# EstlcamShield.net
KiCad netlist of a schematic drawn in EAGLE
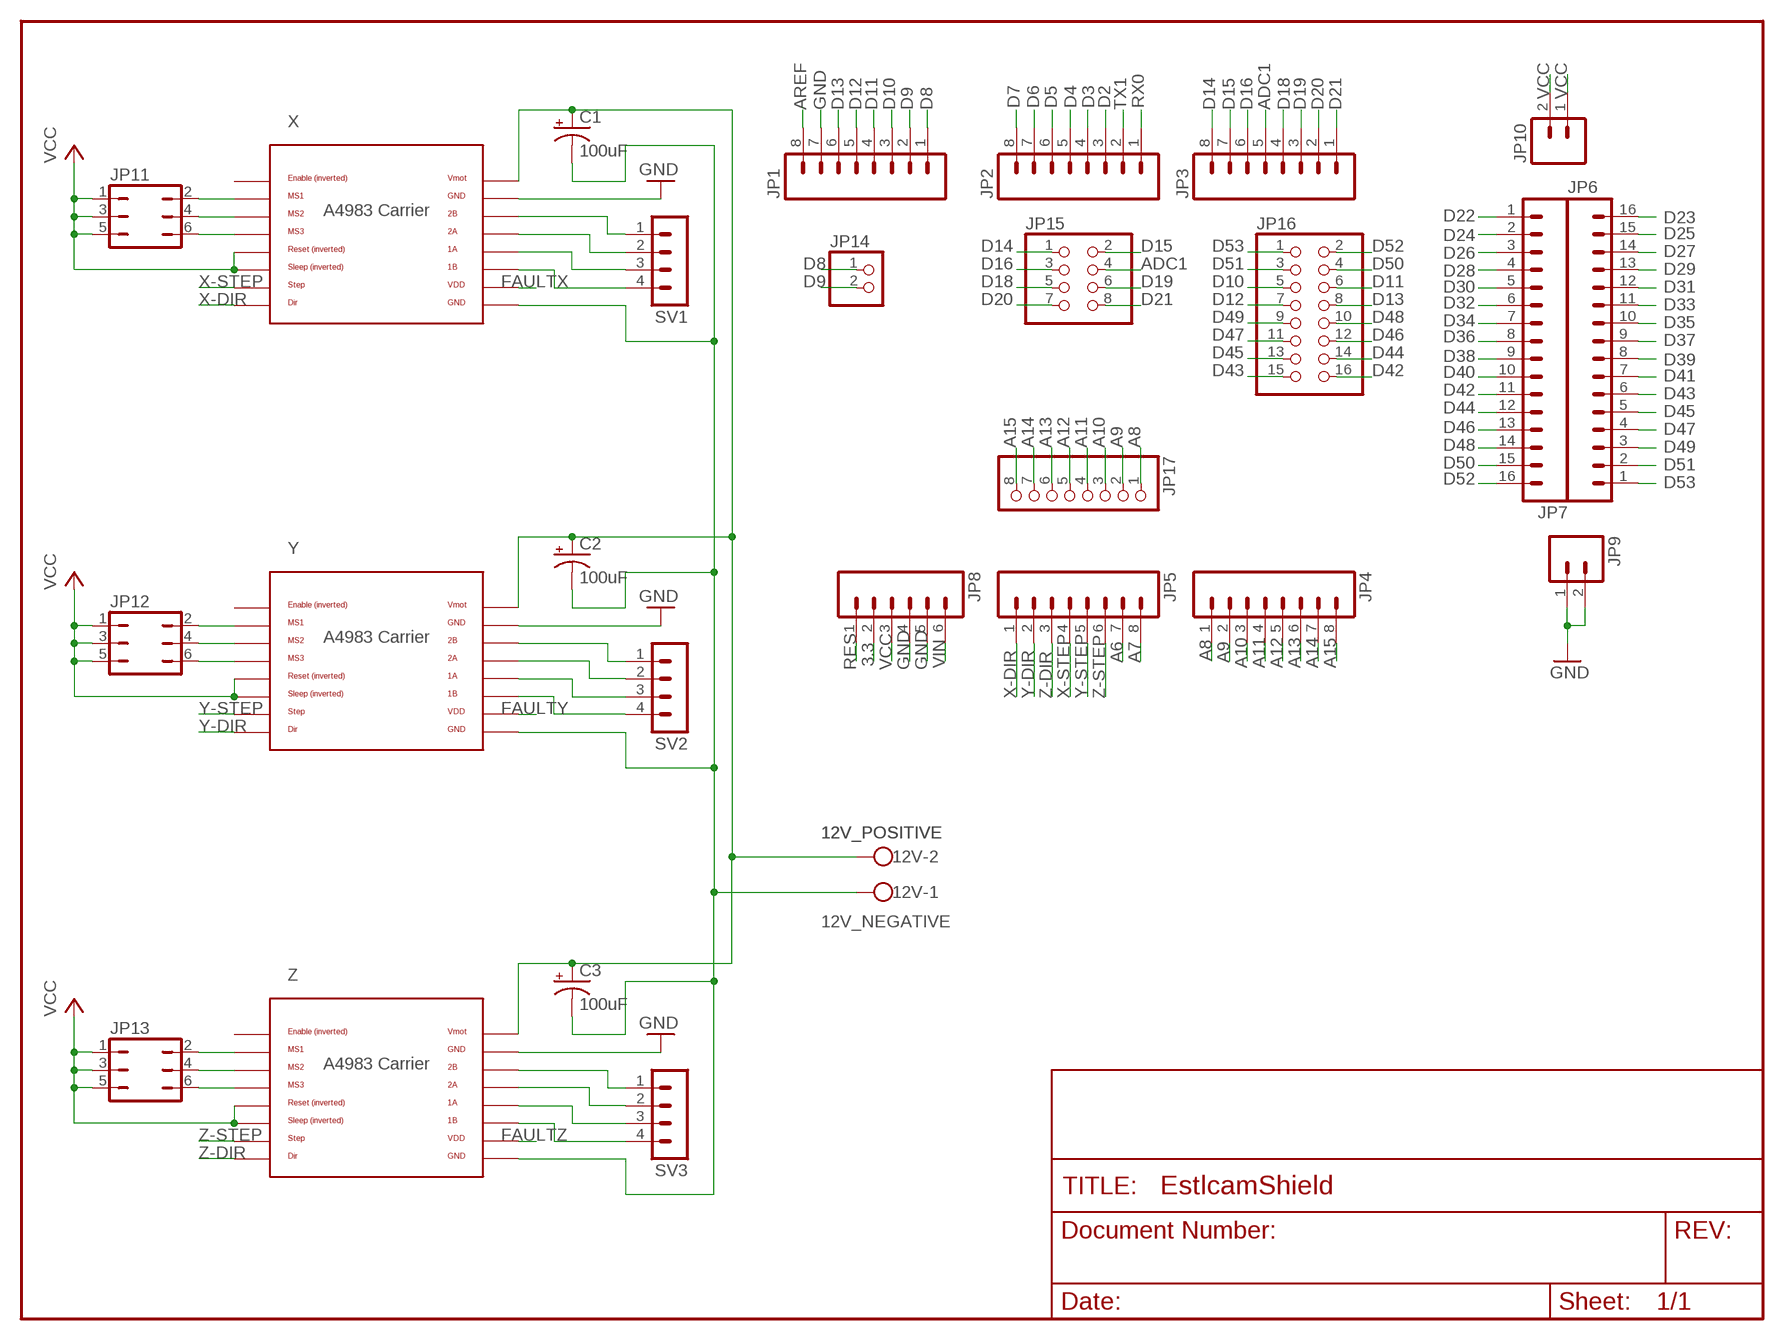
[diagram p0: schematic, sheet 1]

(export (version "E")
  (design (tool "Eeschema 10.0.6"))
  (components
    (comp (ref "12V")
      (value "POSITIVE")
      (footprint "eagle-import:W237-102")
      (fields (field (name "MPN") "237-102"))
      (libsource (lib "eagle-import") (part "W237-102"))
    )
    (comp (ref "C1")
      (value "100uF")
      (footprint "eagle-import:E2,5-5")
      (libsource (lib "eagle-import") (part "CPOL-USE2.5-5"))
    )
    (comp (ref "C2")
      (value "100uF")
      (footprint "eagle-import:E2,5-5")
      (libsource (lib "eagle-import") (part "CPOL-USE2.5-5"))
    )
    (comp (ref "C3")
      (value "100uF")
      (footprint "eagle-import:E2,5-5")
      (libsource (lib "eagle-import") (part "CPOL-USE2.5-5"))
    )
    (comp (ref "JP1")
      (value "M08LOCK")
      (footprint "eagle-import:1X08_LOCK")
      (libsource (lib "eagle-import") (part "M08LOCK"))
    )
    (comp (ref "JP2")
      (value "M08LOCK")
      (footprint "eagle-import:1X08_LOCK")
      (libsource (lib "eagle-import") (part "M08LOCK"))
    )
    (comp (ref "JP3")
      (value "M08LOCK")
      (footprint "eagle-import:1X08_LOCK")
      (libsource (lib "eagle-import") (part "M08LOCK"))
    )
    (comp (ref "JP4")
      (value "M08LOCK")
      (footprint "eagle-import:1X08_LOCK")
      (libsource (lib "eagle-import") (part "M08LOCK"))
    )
    (comp (ref "JP5")
      (value "M08LOCK")
      (footprint "eagle-import:1X08_LOCK")
      (libsource (lib "eagle-import") (part "M08LOCK"))
    )
    (comp (ref "JP6")
      (value "M16LOCK")
      (footprint "eagle-import:1X16_LOCK")
      (libsource (lib "eagle-import") (part "M16LOCK"))
    )
    (comp (ref "JP7")
      (value "M16LOCK")
      (footprint "eagle-import:1X16_LOCK")
      (libsource (lib "eagle-import") (part "M16LOCK"))
    )
    (comp (ref "JP8")
      (value "M06LOCK")
      (footprint "eagle-import:1X06_LOCK")
      (libsource (lib "eagle-import") (part "M06LOCK"))
    )
    (comp (ref "JP9")
      (value "M02LOCK")
      (footprint "eagle-import:1X02_LOCK")
      (libsource (lib "eagle-import") (part "M02LOCK"))
    )
    (comp (ref "JP10")
      (value "M02LOCK")
      (footprint "eagle-import:1X02_LOCK")
      (libsource (lib "eagle-import") (part "M02LOCK"))
    )
    (comp (ref "JP11")
      (value "JP3Q")
      (footprint "eagle-import:JP3Q")
      (libsource (lib "eagle-import") (part "JP3Q"))
    )
    (comp (ref "JP12")
      (value "JP3Q")
      (footprint "eagle-import:JP3Q")
      (libsource (lib "eagle-import") (part "JP3Q"))
    )
    (comp (ref "JP13")
      (value "JP3Q")
      (footprint "eagle-import:JP3Q")
      (libsource (lib "eagle-import") (part "JP3Q"))
    )
    (comp (ref "JP14")
      (value "PINHD-1X2")
      (footprint "eagle-import:1X02")
      (libsource (lib "eagle-import") (part "PINHD-1X2"))
    )
    (comp (ref "JP15")
      (value "PINHD-2X4")
      (footprint "eagle-import:2X04")
      (libsource (lib "eagle-import") (part "PINHD-2X4"))
    )
    (comp (ref "JP16")
      (value "PINHD-2X8")
      (footprint "eagle-import:2X08")
      (libsource (lib "eagle-import") (part "PINHD-2X8"))
    )
    (comp (ref "JP17")
      (value "PINHD-1X8")
      (footprint "eagle-import:1X08")
      (libsource (lib "eagle-import") (part "PINHD-1X8"))
    )
    (comp (ref "SV1")
      (value "MA04-1")
      (footprint "eagle-import:MA04-1")
      (libsource (lib "eagle-import") (part "MA04-1"))
    )
    (comp (ref "SV2")
      (value "MA04-1")
      (footprint "eagle-import:MA04-1")
      (libsource (lib "eagle-import") (part "MA04-1"))
    )
    (comp (ref "SV3")
      (value "MA04-1")
      (footprint "eagle-import:MA04-1")
      (libsource (lib "eagle-import") (part "MA04-1"))
    )
    (comp (ref "U2")
      (value "POLOLU_A4983CARRIER")
      (footprint "eagle-import:A4983CARRIER")
      (libsource (lib "eagle-import") (part "POLOLU_A4983CARRIER"))
    )
    (comp (ref "U3")
      (value "POLOLU_A4983CARRIER")
      (footprint "eagle-import:A4983CARRIER")
      (libsource (lib "eagle-import") (part "POLOLU_A4983CARRIER"))
    )
    (comp (ref "U4")
      (value "POLOLU_A4983CARRIER")
      (footprint "eagle-import:A4983CARRIER")
      (libsource (lib "eagle-import") (part "POLOLU_A4983CARRIER"))
    )
  )
  (nets
    (net (code "1") (name "/3.3") (class "Default")
      (node (ref "JP8") (pin "2") (pinfunction "2_2") (pintype "passive"))
    )
    (net (code "2") (name "/12V_NEGATIVE") (class "Default")
      (node (ref "12V") (pin "1") (pinfunction "KL_1") (pintype "passive"))
      (node (ref "C1") (pin "-") (pinfunction "-_-") (pintype "passive"))
      (node (ref "C2") (pin "-") (pinfunction "-_-") (pintype "passive"))
      (node (ref "C3") (pin "-") (pinfunction "-_-") (pintype "passive"))
      (node (ref "U2") (pin "GND@0") (pinfunction "GND_GND@0") (pintype "power_in"))
      (node (ref "U3") (pin "GND@0") (pinfunction "GND_GND@0") (pintype "power_in"))
      (node (ref "U4") (pin "GND@0") (pinfunction "GND_GND@0") (pintype "power_in"))
    )
    (net (code "3") (name "/12V_POSITIVE") (class "Default")
      (node (ref "12V") (pin "2") (pinfunction "KL_2") (pintype "passive"))
      (node (ref "C1") (pin "+") (pinfunction "+_+") (pintype "passive"))
      (node (ref "C2") (pin "+") (pinfunction "+_+") (pintype "passive"))
      (node (ref "C3") (pin "+") (pinfunction "+_+") (pintype "passive"))
      (node (ref "U2") (pin "VMOT") (pinfunction "VMOT_VMOT") (pintype "power_in"))
      (node (ref "U3") (pin "VMOT") (pinfunction "VMOT_VMOT") (pintype "power_in"))
      (node (ref "U4") (pin "VMOT") (pinfunction "VMOT_VMOT") (pintype "power_in"))
    )
    (net (code "4") (name "/A6") (class "Default")
      (node (ref "JP5") (pin "7") (pinfunction "7_7") (pintype "passive"))
    )
    (net (code "5") (name "/A7") (class "Default")
      (node (ref "JP5") (pin "8") (pinfunction "8_8") (pintype "passive"))
    )
    (net (code "6") (name "/A8") (class "Default")
      (node (ref "JP17") (pin "1") (pinfunction "1_1") (pintype "passive"))
      (node (ref "JP4") (pin "1") (pinfunction "1_1") (pintype "passive"))
    )
    (net (code "7") (name "/A9") (class "Default")
      (node (ref "JP17") (pin "2") (pinfunction "2_2") (pintype "passive"))
      (node (ref "JP4") (pin "2") (pinfunction "2_2") (pintype "passive"))
    )
    (net (code "8") (name "/A10") (class "Default")
      (node (ref "JP17") (pin "3") (pinfunction "3_3") (pintype "passive"))
      (node (ref "JP4") (pin "3") (pinfunction "3_3") (pintype "passive"))
    )
    (net (code "9") (name "/A11") (class "Default")
      (node (ref "JP17") (pin "4") (pinfunction "4_4") (pintype "passive"))
      (node (ref "JP4") (pin "4") (pinfunction "4_4") (pintype "passive"))
    )
    (net (code "10") (name "/A12") (class "Default")
      (node (ref "JP17") (pin "5") (pinfunction "5_5") (pintype "passive"))
      (node (ref "JP4") (pin "5") (pinfunction "5_5") (pintype "passive"))
    )
    (net (code "11") (name "/A13") (class "Default")
      (node (ref "JP17") (pin "6") (pinfunction "6_6") (pintype "passive"))
      (node (ref "JP4") (pin "6") (pinfunction "6_6") (pintype "passive"))
    )
    (net (code "12") (name "/A14") (class "Default")
      (node (ref "JP17") (pin "7") (pinfunction "7_7") (pintype "passive"))
      (node (ref "JP4") (pin "7") (pinfunction "7_7") (pintype "passive"))
    )
    (net (code "13") (name "/A15") (class "Default")
      (node (ref "JP17") (pin "8") (pinfunction "8_8") (pintype "passive"))
      (node (ref "JP4") (pin "8") (pinfunction "8_8") (pintype "passive"))
    )
    (net (code "14") (name "/ADC1") (class "Default")
      (node (ref "JP15") (pin "4") (pinfunction "4_4") (pintype "passive"))
      (node (ref "JP3") (pin "5") (pinfunction "5_5") (pintype "passive"))
    )
    (net (code "15") (name "/AREF") (class "Default")
      (node (ref "JP1") (pin "8") (pinfunction "8_8") (pintype "passive"))
    )
    (net (code "16") (name "/D2") (class "Default")
      (node (ref "JP2") (pin "3") (pinfunction "3_3") (pintype "passive"))
    )
    (net (code "17") (name "/D3") (class "Default")
      (node (ref "JP2") (pin "4") (pinfunction "4_4") (pintype "passive"))
    )
    (net (code "18") (name "/D4") (class "Default")
      (node (ref "JP2") (pin "5") (pinfunction "5_5") (pintype "passive"))
    )
    (net (code "19") (name "/D5") (class "Default")
      (node (ref "JP2") (pin "6") (pinfunction "6_6") (pintype "passive"))
    )
    (net (code "20") (name "/D6") (class "Default")
      (node (ref "JP2") (pin "7") (pinfunction "7_7") (pintype "passive"))
    )
    (net (code "21") (name "/D7") (class "Default")
      (node (ref "JP2") (pin "8") (pinfunction "8_8") (pintype "passive"))
    )
    (net (code "22") (name "/D8") (class "Default")
      (node (ref "JP1") (pin "1") (pinfunction "1_1") (pintype "passive"))
      (node (ref "JP14") (pin "1") (pinfunction "1_1") (pintype "passive"))
    )
    (net (code "23") (name "/D9") (class "Default")
      (node (ref "JP1") (pin "2") (pinfunction "2_2") (pintype "passive"))
      (node (ref "JP14") (pin "2") (pinfunction "2_2") (pintype "passive"))
    )
    (net (code "24") (name "/D10") (class "Default")
      (node (ref "JP1") (pin "3") (pinfunction "3_3") (pintype "passive"))
      (node (ref "JP16") (pin "5") (pinfunction "5_5") (pintype "passive"))
    )
    (net (code "25") (name "/D11") (class "Default")
      (node (ref "JP1") (pin "4") (pinfunction "4_4") (pintype "passive"))
      (node (ref "JP16") (pin "6") (pinfunction "6_6") (pintype "passive"))
    )
    (net (code "26") (name "/D12") (class "Default")
      (node (ref "JP1") (pin "5") (pinfunction "5_5") (pintype "passive"))
      (node (ref "JP16") (pin "7") (pinfunction "7_7") (pintype "passive"))
    )
    (net (code "27") (name "/D13") (class "Default")
      (node (ref "JP1") (pin "6") (pinfunction "6_6") (pintype "passive"))
      (node (ref "JP16") (pin "8") (pinfunction "8_8") (pintype "passive"))
    )
    (net (code "28") (name "/D14") (class "Default")
      (node (ref "JP15") (pin "1") (pinfunction "1_1") (pintype "passive"))
      (node (ref "JP3") (pin "8") (pinfunction "8_8") (pintype "passive"))
    )
    (net (code "29") (name "/D15") (class "Default")
      (node (ref "JP15") (pin "2") (pinfunction "2_2") (pintype "passive"))
      (node (ref "JP3") (pin "7") (pinfunction "7_7") (pintype "passive"))
    )
    (net (code "30") (name "/D16") (class "Default")
      (node (ref "JP15") (pin "3") (pinfunction "3_3") (pintype "passive"))
      (node (ref "JP3") (pin "6") (pinfunction "6_6") (pintype "passive"))
    )
    (net (code "31") (name "/D18") (class "Default")
      (node (ref "JP15") (pin "5") (pinfunction "5_5") (pintype "passive"))
      (node (ref "JP3") (pin "4") (pinfunction "4_4") (pintype "passive"))
    )
    (net (code "32") (name "/D19") (class "Default")
      (node (ref "JP15") (pin "6") (pinfunction "6_6") (pintype "passive"))
      (node (ref "JP3") (pin "3") (pinfunction "3_3") (pintype "passive"))
    )
    (net (code "33") (name "/D20") (class "Default")
      (node (ref "JP15") (pin "7") (pinfunction "7_7") (pintype "passive"))
      (node (ref "JP3") (pin "2") (pinfunction "2_2") (pintype "passive"))
    )
    (net (code "34") (name "/D21") (class "Default")
      (node (ref "JP15") (pin "8") (pinfunction "8_8") (pintype "passive"))
      (node (ref "JP3") (pin "1") (pinfunction "1_1") (pintype "passive"))
    )
    (net (code "35") (name "/D22") (class "Default")
      (node (ref "JP7") (pin "1") (pinfunction "1_1") (pintype "passive"))
    )
    (net (code "36") (name "/D23") (class "Default")
      (node (ref "JP6") (pin "16") (pinfunction "16_16") (pintype "passive"))
    )
    (net (code "37") (name "/D24") (class "Default")
      (node (ref "JP7") (pin "2") (pinfunction "2_2") (pintype "passive"))
    )
    (net (code "38") (name "/D25") (class "Default")
      (node (ref "JP6") (pin "15") (pinfunction "15_15") (pintype "passive"))
    )
    (net (code "39") (name "/D26") (class "Default")
      (node (ref "JP7") (pin "3") (pinfunction "3_3") (pintype "passive"))
    )
    (net (code "40") (name "/D27") (class "Default")
      (node (ref "JP6") (pin "14") (pinfunction "14_14") (pintype "passive"))
    )
    (net (code "41") (name "/D28") (class "Default")
      (node (ref "JP7") (pin "4") (pinfunction "4_4") (pintype "passive"))
    )
    (net (code "42") (name "/D29") (class "Default")
      (node (ref "JP6") (pin "13") (pinfunction "13_13") (pintype "passive"))
    )
    (net (code "43") (name "/D30") (class "Default")
      (node (ref "JP7") (pin "5") (pinfunction "5_5") (pintype "passive"))
    )
    (net (code "44") (name "/D31") (class "Default")
      (node (ref "JP6") (pin "12") (pinfunction "12_12") (pintype "passive"))
    )
    (net (code "45") (name "/D32") (class "Default")
      (node (ref "JP7") (pin "6") (pinfunction "6_6") (pintype "passive"))
    )
    (net (code "46") (name "/D33") (class "Default")
      (node (ref "JP6") (pin "11") (pinfunction "11_11") (pintype "passive"))
    )
    (net (code "47") (name "/D34") (class "Default")
      (node (ref "JP7") (pin "7") (pinfunction "7_7") (pintype "passive"))
    )
    (net (code "48") (name "/D35") (class "Default")
      (node (ref "JP6") (pin "10") (pinfunction "10_10") (pintype "passive"))
    )
    (net (code "49") (name "/D36") (class "Default")
      (node (ref "JP7") (pin "8") (pinfunction "8_8") (pintype "passive"))
    )
    (net (code "50") (name "/D37") (class "Default")
      (node (ref "JP6") (pin "9") (pinfunction "9_9") (pintype "passive"))
    )
    (net (code "51") (name "/D38") (class "Default")
      (node (ref "JP7") (pin "9") (pinfunction "9_9") (pintype "passive"))
    )
    (net (code "52") (name "/D39") (class "Default")
      (node (ref "JP6") (pin "8") (pinfunction "8_8") (pintype "passive"))
    )
    (net (code "53") (name "/D40") (class "Default")
      (node (ref "JP7") (pin "10") (pinfunction "10_10") (pintype "passive"))
    )
    (net (code "54") (name "/D41") (class "Default")
      (node (ref "JP6") (pin "7") (pinfunction "7_7") (pintype "passive"))
    )
    (net (code "55") (name "/D42") (class "Default")
      (node (ref "JP16") (pin "16") (pinfunction "16_16") (pintype "passive"))
      (node (ref "JP7") (pin "11") (pinfunction "11_11") (pintype "passive"))
    )
    (net (code "56") (name "/D43") (class "Default")
      (node (ref "JP16") (pin "15") (pinfunction "15_15") (pintype "passive"))
      (node (ref "JP6") (pin "6") (pinfunction "6_6") (pintype "passive"))
    )
    (net (code "57") (name "/D44") (class "Default")
      (node (ref "JP16") (pin "14") (pinfunction "14_14") (pintype "passive"))
      (node (ref "JP7") (pin "12") (pinfunction "12_12") (pintype "passive"))
    )
    (net (code "58") (name "/D45") (class "Default")
      (node (ref "JP16") (pin "13") (pinfunction "13_13") (pintype "passive"))
      (node (ref "JP6") (pin "5") (pinfunction "5_5") (pintype "passive"))
    )
    (net (code "59") (name "/D46") (class "Default")
      (node (ref "JP16") (pin "12") (pinfunction "12_12") (pintype "passive"))
      (node (ref "JP7") (pin "13") (pinfunction "13_13") (pintype "passive"))
    )
    (net (code "60") (name "/D47") (class "Default")
      (node (ref "JP16") (pin "11") (pinfunction "11_11") (pintype "passive"))
      (node (ref "JP6") (pin "4") (pinfunction "4_4") (pintype "passive"))
    )
    (net (code "61") (name "/D48") (class "Default")
      (node (ref "JP16") (pin "10") (pinfunction "10_10") (pintype "passive"))
      (node (ref "JP7") (pin "14") (pinfunction "14_14") (pintype "passive"))
    )
    (net (code "62") (name "/D49") (class "Default")
      (node (ref "JP16") (pin "9") (pinfunction "9_9") (pintype "passive"))
      (node (ref "JP6") (pin "3") (pinfunction "3_3") (pintype "passive"))
    )
    (net (code "63") (name "/D50") (class "Default")
      (node (ref "JP16") (pin "4") (pinfunction "4_4") (pintype "passive"))
      (node (ref "JP7") (pin "15") (pinfunction "15_15") (pintype "passive"))
    )
    (net (code "64") (name "/D51") (class "Default")
      (node (ref "JP16") (pin "3") (pinfunction "3_3") (pintype "passive"))
      (node (ref "JP6") (pin "2") (pinfunction "2_2") (pintype "passive"))
    )
    (net (code "65") (name "/D52") (class "Default")
      (node (ref "JP16") (pin "2") (pinfunction "2_2") (pintype "passive"))
      (node (ref "JP7") (pin "16") (pinfunction "16_16") (pintype "passive"))
    )
    (net (code "66") (name "/D53") (class "Default")
      (node (ref "JP16") (pin "1") (pinfunction "1_1") (pintype "passive"))
      (node (ref "JP6") (pin "1") (pinfunction "1_1") (pintype "passive"))
    )
    (net (code "67") (name "/FAULTX") (class "Default")
      (node (ref "U2") (pin "VDD") (pinfunction "VDD_VDD") (pintype "power_in"))
    )
    (net (code "68") (name "/FAULTY") (class "Default")
      (node (ref "U3") (pin "VDD") (pinfunction "VDD_VDD") (pintype "power_in"))
    )
    (net (code "69") (name "/FAULTZ") (class "Default")
      (node (ref "U4") (pin "VDD") (pinfunction "VDD_VDD") (pintype "power_in"))
    )
    (net (code "70") (name "/RES") (class "Default")
      (node (ref "JP8") (pin "1") (pinfunction "1_1") (pintype "passive"))
    )
    (net (code "71") (name "/RX0") (class "Default")
      (node (ref "JP2") (pin "1") (pinfunction "1_1") (pintype "passive"))
    )
    (net (code "72") (name "/TX1") (class "Default")
      (node (ref "JP2") (pin "2") (pinfunction "2_2") (pintype "passive"))
    )
    (net (code "73") (name "/VIN") (class "Default")
      (node (ref "JP8") (pin "6") (pinfunction "6_6") (pintype "passive"))
    )
    (net (code "74") (name "/X-DIR") (class "Default")
      (node (ref "JP5") (pin "1") (pinfunction "1_1") (pintype "passive"))
      (node (ref "U2") (pin "DIR") (pinfunction "DIR_DIR") (pintype "input"))
    )
    (net (code "75") (name "/X-STEP") (class "Default")
      (node (ref "JP5") (pin "4") (pinfunction "4_4") (pintype "passive"))
      (node (ref "U2") (pin "STEP") (pinfunction "STEP_STEP") (pintype "input"))
    )
    (net (code "76") (name "/Y-DIR") (class "Default")
      (node (ref "JP5") (pin "2") (pinfunction "2_2") (pintype "passive"))
      (node (ref "U3") (pin "DIR") (pinfunction "DIR_DIR") (pintype "input"))
    )
    (net (code "77") (name "/Y-STEP") (class "Default")
      (node (ref "JP5") (pin "5") (pinfunction "5_5") (pintype "passive"))
      (node (ref "U3") (pin "STEP") (pinfunction "STEP_STEP") (pintype "input"))
    )
    (net (code "78") (name "/Z-DIR") (class "Default")
      (node (ref "JP5") (pin "3") (pinfunction "3_3") (pintype "passive"))
      (node (ref "U4") (pin "DIR") (pinfunction "DIR_DIR") (pintype "input"))
    )
    (net (code "79") (name "/Z-STEP") (class "Default")
      (node (ref "JP5") (pin "6") (pinfunction "6_6") (pintype "passive"))
      (node (ref "U4") (pin "STEP") (pinfunction "STEP_STEP") (pintype "input"))
    )
    (net (code "80") (name "GND") (class "Default")
      (node (ref "JP1") (pin "7") (pinfunction "7_7") (pintype "passive"))
      (node (ref "JP8") (pin "4") (pinfunction "4_4") (pintype "passive"))
      (node (ref "JP8") (pin "5") (pinfunction "5_5") (pintype "passive"))
      (node (ref "JP9") (pin "1") (pinfunction "1_1") (pintype "passive"))
      (node (ref "JP9") (pin "2") (pinfunction "2_2") (pintype "passive"))
      (node (ref "U2") (pin "GND") (pinfunction "GND_GND") (pintype "power_in"))
      (node (ref "U3") (pin "GND") (pinfunction "GND_GND") (pintype "power_in"))
      (node (ref "U4") (pin "GND") (pinfunction "GND_GND") (pintype "power_in"))
    )
    (net (code "81") (name "Net-(JP11-Pad2)") (class "Default")
      (node (ref "JP11") (pin "2") (pinfunction "2_2") (pintype "passive"))
      (node (ref "U2") (pin "MS1") (pinfunction "MS1_MS1") (pintype "input"))
    )
    (net (code "82") (name "Net-(JP11-Pad4)") (class "Default")
      (node (ref "JP11") (pin "4") (pinfunction "4_4") (pintype "passive"))
      (node (ref "U2") (pin "MS2") (pinfunction "MS2_MS2") (pintype "input"))
    )
    (net (code "83") (name "Net-(JP11-Pad6)") (class "Default")
      (node (ref "JP11") (pin "6") (pinfunction "6_6") (pintype "passive"))
      (node (ref "U2") (pin "MS3") (pinfunction "MS3_MS3") (pintype "input"))
    )
    (net (code "84") (name "Net-(JP12-Pad2)") (class "Default")
      (node (ref "JP12") (pin "2") (pinfunction "2_2") (pintype "passive"))
      (node (ref "U3") (pin "MS1") (pinfunction "MS1_MS1") (pintype "input"))
    )
    (net (code "85") (name "Net-(JP12-Pad4)") (class "Default")
      (node (ref "JP12") (pin "4") (pinfunction "4_4") (pintype "passive"))
      (node (ref "U3") (pin "MS2") (pinfunction "MS2_MS2") (pintype "input"))
    )
    (net (code "86") (name "Net-(JP12-Pad6)") (class "Default")
      (node (ref "JP12") (pin "6") (pinfunction "6_6") (pintype "passive"))
      (node (ref "U3") (pin "MS3") (pinfunction "MS3_MS3") (pintype "input"))
    )
    (net (code "87") (name "Net-(JP13-Pad2)") (class "Default")
      (node (ref "JP13") (pin "2") (pinfunction "2_2") (pintype "passive"))
      (node (ref "U4") (pin "MS1") (pinfunction "MS1_MS1") (pintype "input"))
    )
    (net (code "88") (name "Net-(JP13-Pad4)") (class "Default")
      (node (ref "JP13") (pin "4") (pinfunction "4_4") (pintype "passive"))
      (node (ref "U4") (pin "MS2") (pinfunction "MS2_MS2") (pintype "input"))
    )
    (net (code "89") (name "Net-(JP13-Pad6)") (class "Default")
      (node (ref "JP13") (pin "6") (pinfunction "6_6") (pintype "passive"))
      (node (ref "U4") (pin "MS3") (pinfunction "MS3_MS3") (pintype "input"))
    )
    (net (code "90") (name "Net-(SV1-Pad1)") (class "Default")
      (node (ref "SV1") (pin "1") (pinfunction "1_1") (pintype "passive"))
      (node (ref "U2") (pin "2B") (pinfunction "2B_2B") (pintype "output"))
    )
    (net (code "91") (name "Net-(SV1-Pad2)") (class "Default")
      (node (ref "SV1") (pin "2") (pinfunction "2_2") (pintype "passive"))
      (node (ref "U2") (pin "2A") (pinfunction "2A_2A") (pintype "output"))
    )
    (net (code "92") (name "Net-(SV1-Pad3)") (class "Default")
      (node (ref "SV1") (pin "3") (pinfunction "3_3") (pintype "passive"))
      (node (ref "U2") (pin "1A") (pinfunction "1A_1A") (pintype "output"))
    )
    (net (code "93") (name "Net-(SV1-Pad4)") (class "Default")
      (node (ref "SV1") (pin "4") (pinfunction "4_4") (pintype "passive"))
      (node (ref "U2") (pin "1B") (pinfunction "1B_1B") (pintype "output"))
    )
    (net (code "94") (name "Net-(SV2-Pad1)") (class "Default")
      (node (ref "SV2") (pin "1") (pinfunction "1_1") (pintype "passive"))
      (node (ref "U3") (pin "2B") (pinfunction "2B_2B") (pintype "output"))
    )
    (net (code "95") (name "Net-(SV2-Pad2)") (class "Default")
      (node (ref "SV2") (pin "2") (pinfunction "2_2") (pintype "passive"))
      (node (ref "U3") (pin "2A") (pinfunction "2A_2A") (pintype "output"))
    )
    (net (code "96") (name "Net-(SV2-Pad3)") (class "Default")
      (node (ref "SV2") (pin "3") (pinfunction "3_3") (pintype "passive"))
      (node (ref "U3") (pin "1A") (pinfunction "1A_1A") (pintype "output"))
    )
    (net (code "97") (name "Net-(SV2-Pad4)") (class "Default")
      (node (ref "SV2") (pin "4") (pinfunction "4_4") (pintype "passive"))
      (node (ref "U3") (pin "1B") (pinfunction "1B_1B") (pintype "output"))
    )
    (net (code "98") (name "Net-(SV3-Pad1)") (class "Default")
      (node (ref "SV3") (pin "1") (pinfunction "1_1") (pintype "passive"))
      (node (ref "U4") (pin "2B") (pinfunction "2B_2B") (pintype "output"))
    )
    (net (code "99") (name "Net-(SV3-Pad2)") (class "Default")
      (node (ref "SV3") (pin "2") (pinfunction "2_2") (pintype "passive"))
      (node (ref "U4") (pin "2A") (pinfunction "2A_2A") (pintype "output"))
    )
    (net (code "100") (name "Net-(SV3-Pad3)") (class "Default")
      (node (ref "SV3") (pin "3") (pinfunction "3_3") (pintype "passive"))
      (node (ref "U4") (pin "1A") (pinfunction "1A_1A") (pintype "output"))
    )
    (net (code "101") (name "Net-(SV3-Pad4)") (class "Default")
      (node (ref "SV3") (pin "4") (pinfunction "4_4") (pintype "passive"))
      (node (ref "U4") (pin "1B") (pinfunction "1B_1B") (pintype "output"))
    )
    (net (code "102") (name "VCC") (class "Default")
      (node (ref "JP10") (pin "1") (pinfunction "1_1") (pintype "passive"))
      (node (ref "JP10") (pin "2") (pinfunction "2_2") (pintype "passive"))
      (node (ref "JP11") (pin "1") (pinfunction "1_1") (pintype "passive"))
      (node (ref "JP11") (pin "3") (pinfunction "3_3") (pintype "passive"))
      (node (ref "JP11") (pin "5") (pinfunction "5_5") (pintype "passive"))
      (node (ref "JP12") (pin "1") (pinfunction "1_1") (pintype "passive"))
      (node (ref "JP12") (pin "3") (pinfunction "3_3") (pintype "passive"))
      (node (ref "JP12") (pin "5") (pinfunction "5_5") (pintype "passive"))
      (node (ref "JP13") (pin "1") (pinfunction "1_1") (pintype "passive"))
      (node (ref "JP13") (pin "3") (pinfunction "3_3") (pintype "passive"))
      (node (ref "JP13") (pin "5") (pinfunction "5_5") (pintype "passive"))
      (node (ref "JP8") (pin "3") (pinfunction "3_3") (pintype "passive"))
      (node (ref "U2") (pin "RST") (pinfunction "RST_RST") (pintype "input"))
      (node (ref "U2") (pin "SLP") (pinfunction "SLEEP_SLP") (pintype "input"))
      (node (ref "U3") (pin "RST") (pinfunction "RST_RST") (pintype "input"))
      (node (ref "U3") (pin "SLP") (pinfunction "SLEEP_SLP") (pintype "input"))
      (node (ref "U4") (pin "RST") (pinfunction "RST_RST") (pintype "input"))
      (node (ref "U4") (pin "SLP") (pinfunction "SLEEP_SLP") (pintype "input"))
    )
    (net (code "103") (name "unconnected-(U2-PadEN)") (class "Default")
      (node (ref "U2") (pin "EN") (pinfunction "EN_EN") (pintype "input"))
    )
    (net (code "104") (name "unconnected-(U3-PadEN)") (class "Default")
      (node (ref "U3") (pin "EN") (pinfunction "EN_EN") (pintype "input"))
    )
    (net (code "105") (name "unconnected-(U4-PadEN)") (class "Default")
      (node (ref "U4") (pin "EN") (pinfunction "EN_EN") (pintype "input"))
    )
  )
)
